# Motors.net
KiCad netlist of a schematic drawn in Altium Designer
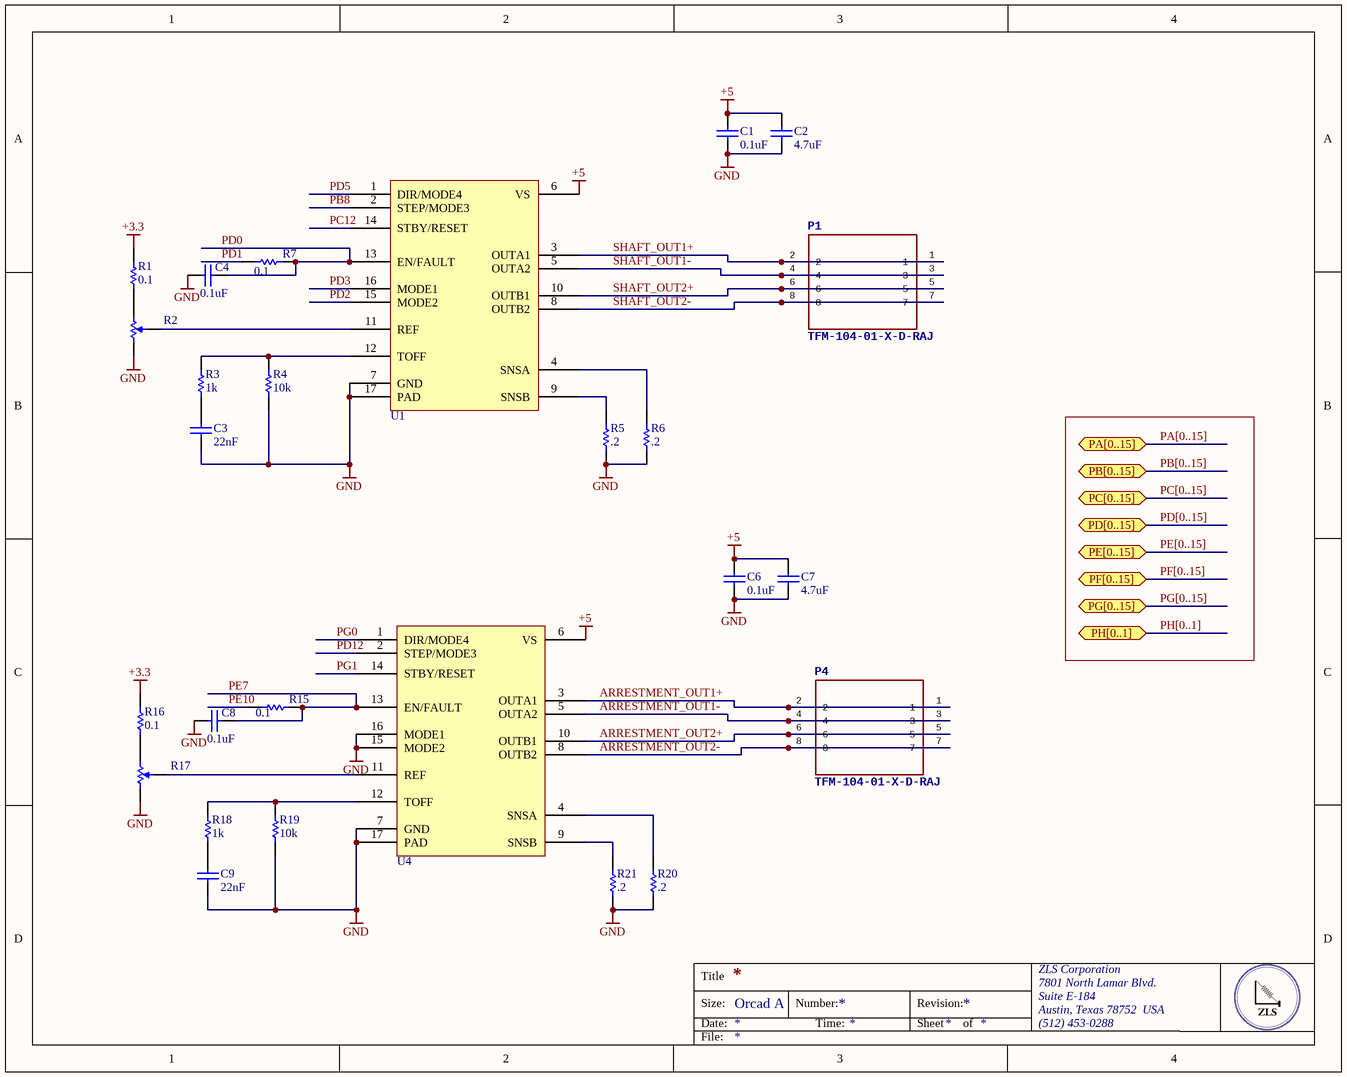
[diagram p0: Motors.SchDoc]

(export (version "E")
  (design (tool "Eeschema 10.0.6"))
  (components
    (comp (ref "C1")
      (value "0.1uF")
      (footprint "CAPC1608X94X35LL15T15")
      (description "CAP .1UF 16V CERAMIC X7R 0603")
      (fields
        (field (name "MANUFACTURER") "Yageo")
        (field (name "MANUFACTURER PART NUMBER") "CC0603KRX7R7BB105")
      )
      (libsource (lib "Altium Content Vault") (part "CAP-NP-2"))
    )
    (comp (ref "C2")
      (value "4.7uF")
      (footprint "CAPC0603(1608)55_M")
      (description "CAP 4.7uF 6.3V ±10% 0603 (1608 Metric) Thickness 0.55mm SMD")
      (fields (field (name "TOLERANCE") "Â±10%") (field (name "MANUFACTURER") "KEMET"))
      (libsource (lib "Altium Content Vault") (part "CAP"))
    )
    (comp (ref "C3")
      (value "22nF")
      (footprint "CAPC1608X94X35LL15T15")
      (description "CAP .1UF 16V CERAMIC X7R 0603")
      (fields
        (field (name "MANUFACTURER") "Yageo")
        (field (name "MANUFACTURER PART NUMBER") "CC0603KRX7R7BB105")
      )
      (libsource (lib "Altium Content Vault") (part "CMP-1661-00001-2"))
    )
    (comp (ref "C4")
      (value "0.1uF")
      (footprint "CAPC1608X94X35LL15T15")
      (description "CAP .1UF 16V CERAMIC X7R 0603")
      (fields
        (field (name "MANUFACTURER") "Yageo")
        (field (name "MANUFACTURER PART NUMBER") "CC0603KRX7R7BB105")
      )
      (libsource (lib "Altium Content Vault") (part "CAP-NP-2"))
    )
    (comp (ref "C6")
      (value "0.1uF")
      (footprint "CAPC1608X94X35LL15T15")
      (description "CAP .1UF 16V CERAMIC X7R 0603")
      (fields
        (field (name "MANUFACTURER") "Yageo")
        (field (name "MANUFACTURER PART NUMBER") "CC0603KRX7R7BB105")
      )
      (libsource (lib "Altium Content Vault") (part "CAP-NP-2"))
    )
    (comp (ref "C7")
      (value "4.7uF")
      (footprint "CAPC0603(1608)55_M")
      (description "CAP 4.7uF 6.3V ±10% 0603 (1608 Metric) Thickness 0.55mm SMD")
      (fields (field (name "TOLERANCE") "Â±10%") (field (name "MANUFACTURER") "KEMET"))
      (libsource (lib "Altium Content Vault") (part "CAP"))
    )
    (comp (ref "C8")
      (value "0.1uF")
      (footprint "CAPC1608X94X35LL15T15")
      (description "CAP .1UF 16V CERAMIC X7R 0603")
      (fields
        (field (name "MANUFACTURER") "Yageo")
        (field (name "MANUFACTURER PART NUMBER") "CC0603KRX7R7BB105")
      )
      (libsource (lib "Altium Content Vault") (part "CAP-NP-2"))
    )
    (comp (ref "C9")
      (value "22nF")
      (footprint "CAPC1608X94X35LL15T15")
      (description "CAP .1UF 16V CERAMIC X7R 0603")
      (fields
        (field (name "MANUFACTURER") "Yageo")
        (field (name "MANUFACTURER PART NUMBER") "CC0603KRX7R7BB105")
      )
      (libsource (lib "Altium Content Vault") (part "CMP-1661-00001-2"))
    )
    (comp (ref "P1")
      (value "TFM-104-01-X-D-RAJ")
      (footprint "SAMTEC-TFM-104-01-X-D-RA")
      (fields (field (name "MANUFACTURER") "SAMTEC"))
      (libsource (lib "SAMTEC-TFM-104-01-X-D-RA") (part "SAMTEC-TFM-104-01-X-D-RAJ"))
    )
    (comp (ref "P4")
      (value "TFM-104-01-X-D-RAJ")
      (footprint "SAMTEC-TFM-104-01-X-D-RA")
      (fields (field (name "MANUFACTURER") "SAMTEC"))
      (libsource (lib "SAMTEC-TFM-104-01-X-D-RA") (part "SAMTEC-TFM-104-01-X-D-RAJ"))
    )
    (comp (ref "R1")
      (value "0.1")
      (footprint "RESC0603(1608)_N")
      (description "RES 0.1 OHM 1% 1/10W 0603")
      (fields
        (field (name "MANUFACTURER") "Bourns")
        (field (name "MANUFACTURER PART NUMBER") "CRL0603-FW-R100ELF")
      )
      (libsource (lib "Altium Content Vault") (part "RES"))
    )
    (comp (ref "R2")
      (value "3313J-1-503E")
      (footprint "BOUR-3313J-1_V")
      (fields (field (name "MANUFACTURER") "Bourns") (field (name "TOLERANCE") "20%"))
      (libsource (lib "Altium Content Vault") (part "CMP-2000-05588-1"))
    )
    (comp (ref "R3")
      (value "1k")
      (footprint "RESC0603(1608)_N")
      (description "RES SMD 1K OHM 0.1% 1/10W 0603")
      (fields
        (field (name "MANUFACTURER") "Panasonic")
        (field (name "MANUFACTURER PART NUMBER") "ERA-3AEB102V")
      )
      (libsource (lib "Altium Content Vault") (part "RES"))
    )
    (comp (ref "R4")
      (value "10k")
      (footprint "RESC0603(1608)_N")
      (description "0R12 0.1W 1% 0603 (1608 Metric)  SMD")
      (fields (field (name "POWER") "0.1 W") (field (name "TOLERANCE") "1 %"))
      (libsource (lib "Altium Content Vault") (part "RES"))
    )
    (comp (ref "R5")
      (value ".2")
      (footprint "RESC0603(1608)_N")
      (description "RES 0.1W 1% 0603 (1608 Metric)  SMD")
      (fields
        (field (name "MANUFACTURER") "Bourns")
        (field (name "MANUFACTURER PART NUMBER") "CRL0603-FW-R200ELF")
      )
      (libsource (lib "Altium Content Vault") (part "RES"))
    )
    (comp (ref "R6")
      (value ".2")
      (footprint "RESC0603(1608)_N")
      (description "RES 0.1W 1% 0603 (1608 Metric)  SMD")
      (fields
        (field (name "MANUFACTURER") "Bourns")
        (field (name "MANUFACTURER PART NUMBER") "CRL0603-FW-R200ELF")
      )
      (libsource (lib "Altium Content Vault") (part "RES"))
    )
    (comp (ref "R7")
      (value "0.1")
      (footprint "RESC0603(1608)_N")
      (description "RES 0.1 OHM 1% 1/10W 0603")
      (fields
        (field (name "MANUFACTURER") "Bourns")
        (field (name "MANUFACTURER PART NUMBER") "CRL0603-FW-R100ELF")
      )
      (libsource (lib "Altium Content Vault") (part "RES"))
    )
    (comp (ref "R15")
      (value "0.1")
      (footprint "RESC0603(1608)_N")
      (description "RES 0.1 OHM 1% 1/10W 0603")
      (fields
        (field (name "MANUFACTURER") "Bourns")
        (field (name "MANUFACTURER PART NUMBER") "CRL0603-FW-R100ELF")
      )
      (libsource (lib "Altium Content Vault") (part "RES"))
    )
    (comp (ref "R16")
      (value "0.1")
      (footprint "RESC0603(1608)_N")
      (description "RES 0.1 OHM 1% 1/10W 0603")
      (fields
        (field (name "MANUFACTURER") "Bourns")
        (field (name "MANUFACTURER PART NUMBER") "CRL0603-FW-R100ELF")
      )
      (libsource (lib "Altium Content Vault") (part "RES"))
    )
    (comp (ref "R17")
      (value "3313J-1-503E")
      (footprint "BOUR-3313J-1_V")
      (fields (field (name "MANUFACTURER") "Bourns") (field (name "TOLERANCE") "20%"))
      (libsource (lib "Altium Content Vault") (part "CMP-2000-05588-1"))
    )
    (comp (ref "R18")
      (value "1k")
      (footprint "RESC0603(1608)_N")
      (description "RES SMD 1K OHM 0.1% 1/10W 0603")
      (fields
        (field (name "MANUFACTURER") "Panasonic")
        (field (name "MANUFACTURER PART NUMBER") "ERA-3AEB102V")
      )
      (libsource (lib "Altium Content Vault") (part "RES"))
    )
    (comp (ref "R19")
      (value "10k")
      (footprint "RESC0603(1608)_N")
      (description "0R12 0.1W 1% 0603 (1608 Metric)  SMD")
      (fields (field (name "POWER") "0.1 W") (field (name "TOLERANCE") "1 %"))
      (libsource (lib "Altium Content Vault") (part "RES"))
    )
    (comp (ref "R20")
      (value ".2")
      (footprint "RESC0603(1608)_N")
      (description "RES 0.1W 1% 0603 (1608 Metric)  SMD")
      (fields
        (field (name "MANUFACTURER") "Bourns")
        (field (name "MANUFACTURER PART NUMBER") "CRL0603-FW-R200ELF")
      )
      (libsource (lib "Altium Content Vault") (part "RES"))
    )
    (comp (ref "R21")
      (value ".2")
      (footprint "RESC0603(1608)_N")
      (description "RES 0.1W 1% 0603 (1608 Metric)  SMD")
      (fields
        (field (name "MANUFACTURER") "Bourns")
        (field (name "MANUFACTURER PART NUMBER") "CRL0603-FW-R200ELF")
      )
      (libsource (lib "Altium Content Vault") (part "RES"))
    )
    (comp (ref "U1")
      (value "STSPIN220")
      (footprint "STSPIN220-QFN127P600-8N")
      (description "LOW VOLTAGE STEPPER MOTOR DRIVER")
      (fields (field (name "MANUFACTURER") "STMicroelectronics"))
      (libsource (lib "ZLS_Schematic_lib") (part "STSPIN220"))
    )
    (comp (ref "U4")
      (value "STSPIN220")
      (footprint "STSPIN220-QFN127P600-8N")
      (description "LOW VOLTAGE STEPPER MOTOR DRIVER")
      (fields (field (name "MANUFACTURER") "STMicroelectronics"))
      (libsource (lib "ZLS_Schematic_lib") (part "STSPIN220"))
    )
  )
  (nets
    (net (code "103") (name "+3.3") (class "Default")
      (node (ref "R1") (pin "1") (pinfunction "1_1") (pintype "passive"))
      (node (ref "R16") (pin "1") (pinfunction "1_1") (pintype "passive"))
    )
    (net (code "104") (name "+5") (class "Default")
      (node (ref "C1") (pin "1") (pinfunction "1_1") (pintype "passive"))
      (node (ref "C2") (pin "2") (pinfunction "2_2") (pintype "passive"))
      (node (ref "C6") (pin "1") (pinfunction "1_1") (pintype "passive"))
      (node (ref "C7") (pin "2") (pinfunction "2_2") (pintype "passive"))
      (node (ref "U1") (pin "6") (pinfunction "VS_6") (pintype "passive"))
      (node (ref "U4") (pin "6") (pinfunction "VS_6") (pintype "passive"))
    )
    (net (code "105") (name "/ARRESTMENT_OUT1+") (class "Default")
      (node (ref "P4") (pin "1") (pinfunction "1_1") (pintype "passive"))
      (node (ref "P4") (pin "2") (pinfunction "2_2") (pintype "passive"))
      (node (ref "U4") (pin "3") (pinfunction "OUTA1_3") (pintype "passive"))
    )
    (net (code "106") (name "/ARRESTMENT_OUT1-") (class "Default")
      (node (ref "P4") (pin "3") (pinfunction "3_3") (pintype "passive"))
      (node (ref "P4") (pin "4") (pinfunction "4_4") (pintype "passive"))
      (node (ref "U4") (pin "5") (pinfunction "OUTA2_5") (pintype "passive"))
    )
    (net (code "107") (name "/ARRESTMENT_OUT2+") (class "Default")
      (node (ref "P4") (pin "5") (pinfunction "5_5") (pintype "passive"))
      (node (ref "P4") (pin "6") (pinfunction "6_6") (pintype "passive"))
      (node (ref "U4") (pin "10") (pinfunction "OUTB1_10") (pintype "passive"))
    )
    (net (code "108") (name "/ARRESTMENT_OUT2-") (class "Default")
      (node (ref "P4") (pin "7") (pinfunction "7_7") (pintype "passive"))
      (node (ref "P4") (pin "8") (pinfunction "8_8") (pintype "passive"))
      (node (ref "U4") (pin "8") (pinfunction "OUTB2_8") (pintype "passive"))
    )
    (net (code "110") (name "/PB8") (class "Default")
      (node (ref "U1") (pin "2") (pinfunction "STEP/MODE3_2") (pintype "passive"))
    )
    (net (code "112") (name "/PC12") (class "Default")
      (node (ref "U1") (pin "14") (pinfunction "STBY/RESET_14") (pintype "passive"))
    )
    (net (code "114") (name "/PD0") (class "Default")
      (node (ref "C4") (pin "2") (pinfunction "2_2") (pintype "passive"))
      (node (ref "R7") (pin "1") (pinfunction "1_1") (pintype "passive"))
      (node (ref "U1") (pin "13") (pinfunction "EN/FAULT_13") (pintype "passive"))
    )
    (net (code "115") (name "/PD1") (class "Default")
      (node (ref "R7") (pin "2") (pinfunction "2_2") (pintype "passive"))
    )
    (net (code "116") (name "/PD2") (class "Default")
      (node (ref "U1") (pin "15") (pinfunction "MODE2_15") (pintype "passive"))
    )
    (net (code "117") (name "/PD3") (class "Default")
      (node (ref "U1") (pin "16") (pinfunction "MODE1_16") (pintype "passive"))
    )
    (net (code "118") (name "/PD5") (class "Default")
      (node (ref "U1") (pin "1") (pinfunction "DIR/MODE4_1") (pintype "passive"))
    )
    (net (code "119") (name "/PD12") (class "Default")
      (node (ref "U4") (pin "2") (pinfunction "STEP/MODE3_2") (pintype "passive"))
    )
    (net (code "121") (name "/PE7") (class "Default")
      (node (ref "C8") (pin "2") (pinfunction "2_2") (pintype "passive"))
      (node (ref "R15") (pin "1") (pinfunction "1_1") (pintype "passive"))
      (node (ref "U4") (pin "13") (pinfunction "EN/FAULT_13") (pintype "passive"))
    )
    (net (code "122") (name "/PE10") (class "Default")
      (node (ref "R15") (pin "2") (pinfunction "2_2") (pintype "passive"))
    )
    (net (code "125") (name "/PG0") (class "Default")
      (node (ref "U4") (pin "1") (pinfunction "DIR/MODE4_1") (pintype "passive"))
    )
    (net (code "126") (name "/PG1") (class "Default")
      (node (ref "U4") (pin "14") (pinfunction "STBY/RESET_14") (pintype "passive"))
    )
    (net (code "129") (name "/SHAFT_OUT1+") (class "Default")
      (node (ref "P1") (pin "1") (pinfunction "1_1") (pintype "passive"))
      (node (ref "P1") (pin "2") (pinfunction "2_2") (pintype "passive"))
      (node (ref "U1") (pin "3") (pinfunction "OUTA1_3") (pintype "passive"))
    )
    (net (code "130") (name "/SHAFT_OUT1-") (class "Default")
      (node (ref "P1") (pin "3") (pinfunction "3_3") (pintype "passive"))
      (node (ref "P1") (pin "4") (pinfunction "4_4") (pintype "passive"))
      (node (ref "U1") (pin "5") (pinfunction "OUTA2_5") (pintype "passive"))
    )
    (net (code "131") (name "/SHAFT_OUT2+") (class "Default")
      (node (ref "P1") (pin "5") (pinfunction "5_5") (pintype "passive"))
      (node (ref "P1") (pin "6") (pinfunction "6_6") (pintype "passive"))
      (node (ref "U1") (pin "10") (pinfunction "OUTB1_10") (pintype "passive"))
    )
    (net (code "132") (name "/SHAFT_OUT2-") (class "Default")
      (node (ref "P1") (pin "7") (pinfunction "7_7") (pintype "passive"))
      (node (ref "P1") (pin "8") (pinfunction "8_8") (pintype "passive"))
      (node (ref "U1") (pin "8") (pinfunction "OUTB2_8") (pintype "passive"))
    )
    (net (code "133") (name "GND") (class "Default")
      (node (ref "C1") (pin "2") (pinfunction "2_2") (pintype "passive"))
      (node (ref "C2") (pin "1") (pinfunction "1_1") (pintype "passive"))
      (node (ref "C3") (pin "2") (pinfunction "2_2") (pintype "passive"))
      (node (ref "C4") (pin "1") (pinfunction "1_1") (pintype "passive"))
      (node (ref "C6") (pin "2") (pinfunction "2_2") (pintype "passive"))
      (node (ref "C7") (pin "1") (pinfunction "1_1") (pintype "passive"))
      (node (ref "C8") (pin "1") (pinfunction "1_1") (pintype "passive"))
      (node (ref "C9") (pin "2") (pinfunction "2_2") (pintype "passive"))
      (node (ref "R17") (pin "1") (pinfunction "1_1") (pintype "passive"))
      (node (ref "R19") (pin "1") (pinfunction "1_1") (pintype "passive"))
      (node (ref "R2") (pin "1") (pinfunction "1_1") (pintype "passive"))
      (node (ref "R20") (pin "1") (pinfunction "1_1") (pintype "passive"))
      (node (ref "R21") (pin "1") (pinfunction "1_1") (pintype "passive"))
      (node (ref "R4") (pin "1") (pinfunction "1_1") (pintype "passive"))
      (node (ref "R5") (pin "1") (pinfunction "1_1") (pintype "passive"))
      (node (ref "R6") (pin "1") (pinfunction "1_1") (pintype "passive"))
      (node (ref "U1") (pin "17") (pinfunction "PAD_17") (pintype "passive"))
      (node (ref "U1") (pin "7") (pinfunction "GND_7") (pintype "passive"))
      (node (ref "U4") (pin "15") (pinfunction "MODE2_15") (pintype "passive"))
      (node (ref "U4") (pin "16") (pinfunction "MODE1_16") (pintype "passive"))
      (node (ref "U4") (pin "17") (pinfunction "PAD_17") (pintype "passive"))
      (node (ref "U4") (pin "7") (pinfunction "GND_7") (pintype "passive"))
    )
    (net (code "134") (name "Net-(C3-Pad1)") (class "Default")
      (node (ref "C3") (pin "1") (pinfunction "1_1") (pintype "passive"))
      (node (ref "R3") (pin "1") (pinfunction "1_1") (pintype "passive"))
    )
    (net (code "135") (name "Net-(C9-Pad1)") (class "Default")
      (node (ref "C9") (pin "1") (pinfunction "1_1") (pintype "passive"))
      (node (ref "R18") (pin "1") (pinfunction "1_1") (pintype "passive"))
    )
    (net (code "136") (name "Net-(R1-Pad2)") (class "Default")
      (node (ref "R1") (pin "2") (pinfunction "2_2") (pintype "passive"))
      (node (ref "R2") (pin "3") (pinfunction "3_3") (pintype "passive"))
    )
    (net (code "137") (name "Net-(R16-Pad2)") (class "Default")
      (node (ref "R16") (pin "2") (pinfunction "2_2") (pintype "passive"))
      (node (ref "R17") (pin "3") (pinfunction "3_3") (pintype "passive"))
    )
    (net (code "138") (name "Net-(U1-REF)") (class "Default")
      (node (ref "R2") (pin "2") (pinfunction "2_2") (pintype "passive"))
      (node (ref "U1") (pin "11") (pinfunction "REF_11") (pintype "passive"))
    )
    (net (code "139") (name "Net-(U1-SNSA)") (class "Default")
      (node (ref "R6") (pin "2") (pinfunction "2_2") (pintype "passive"))
      (node (ref "U1") (pin "4") (pinfunction "SNSA_4") (pintype "passive"))
    )
    (net (code "140") (name "Net-(U1-SNSB)") (class "Default")
      (node (ref "R5") (pin "2") (pinfunction "2_2") (pintype "passive"))
      (node (ref "U1") (pin "9") (pinfunction "SNSB_9") (pintype "passive"))
    )
    (net (code "141") (name "Net-(U1-TOFF)") (class "Default")
      (node (ref "R3") (pin "2") (pinfunction "2_2") (pintype "passive"))
      (node (ref "R4") (pin "2") (pinfunction "2_2") (pintype "passive"))
      (node (ref "U1") (pin "12") (pinfunction "TOFF_12") (pintype "passive"))
    )
    (net (code "142") (name "Net-(U4-REF)") (class "Default")
      (node (ref "R17") (pin "2") (pinfunction "2_2") (pintype "passive"))
      (node (ref "U4") (pin "11") (pinfunction "REF_11") (pintype "passive"))
    )
    (net (code "143") (name "Net-(U4-SNSA)") (class "Default")
      (node (ref "R20") (pin "2") (pinfunction "2_2") (pintype "passive"))
      (node (ref "U4") (pin "4") (pinfunction "SNSA_4") (pintype "passive"))
    )
    (net (code "144") (name "Net-(U4-SNSB)") (class "Default")
      (node (ref "R21") (pin "2") (pinfunction "2_2") (pintype "passive"))
      (node (ref "U4") (pin "9") (pinfunction "SNSB_9") (pintype "passive"))
    )
    (net (code "145") (name "Net-(U4-TOFF)") (class "Default")
      (node (ref "R18") (pin "2") (pinfunction "2_2") (pintype "passive"))
      (node (ref "R19") (pin "2") (pinfunction "2_2") (pintype "passive"))
      (node (ref "U4") (pin "12") (pinfunction "TOFF_12") (pintype "passive"))
    )
  )
)
